# ST7789_Sheet.net
KiCad netlist of a schematic drawn in Altium Designer
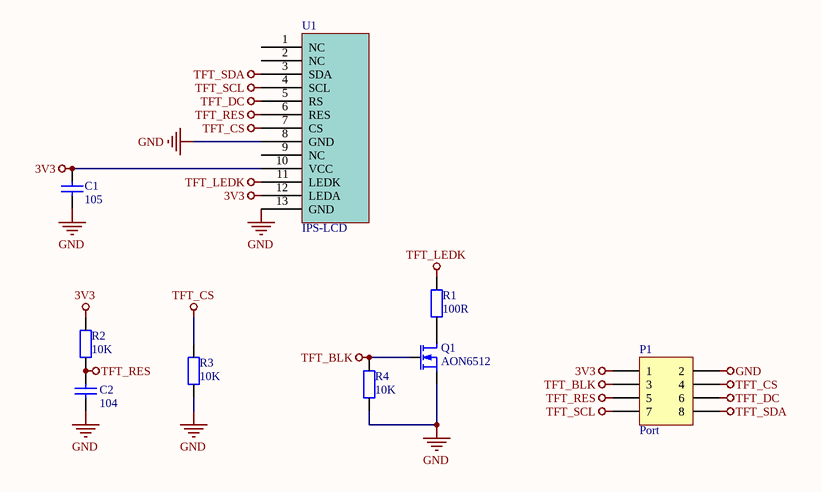
[diagram p0: ST7789_Sheet.SchDoc]

(export (version "E")
  (design (tool "Eeschema 10.0.6"))
  (components
    (comp (ref "C1")
      (value "105")
      (footprint "电容_C0603")
      (fields (field (name "C") "105"))
      (libsource (lib "元件库") (part "cap"))
    )
    (comp (ref "C2")
      (value "104")
      (footprint "电容_C0603")
      (fields (field (name "C") "104"))
      (libsource (lib "元件库") (part "cap"))
    )
    (comp (ref "P1")
      (value "Port")
      (footprint "HDR2X4")
      (description "Header, 4-Pin, Dual row")
      (fields (field (name "PUBLISHER") "Altium Limited"))
      (libsource (lib "Miscellaneous Connectors") (part "Header 4X2"))
    )
    (comp (ref "Q1") (value "AON6512") (footprint "MOS_SOT-23") (libsource (lib "元件库") (part "MOSFET-N")))
    (comp (ref "R1")
      (value "100R")
      (footprint "电阻_R0603")
      (fields (field (name "_VALUE") "100R"))
      (libsource (lib "元件库") (part "Res"))
    )
    (comp (ref "R2")
      (value "10K")
      (footprint "电阻_R0603")
      (fields (field (name "R") "10K"))
      (libsource (lib "元件库") (part "Res"))
    )
    (comp (ref "R3")
      (value "10K")
      (footprint "电阻_R0603")
      (fields (field (name "R") "10K"))
      (libsource (lib "元件库") (part "Res"))
    )
    (comp (ref "R4")
      (value "10K")
      (footprint "电阻_R0603")
      (fields (field (name "R") "10K"))
      (libsource (lib "元件库") (part "Res"))
    )
    (comp (ref "U1")
      (value "IPS-LCD")
      (footprint "TriggersLib:1.14IPS-LCD")
      (description "IPS-LCD-1.14寸裸屏spi接口")
      (libsource (lib "TriggersLib") (part "IPS-LCD-1.14"))
    )
  )
  (nets
    (net (code "1") (name "3V3") (class "Default")
      (node (ref "C1") (pin "2") (pinfunction "2_2") (pintype "passive"))
      (node (ref "P1") (pin "1") (pinfunction "1_1") (pintype "passive"))
      (node (ref "R2") (pin "2") (pinfunction "2_2") (pintype "passive"))
      (node (ref "U1") (pin "10") (pinfunction "VCC_10") (pintype "passive"))
      (node (ref "U1") (pin "12") (pinfunction "LEDA_12") (pintype "passive"))
    )
    (net (code "2") (name "GND") (class "Default")
      (node (ref "C1") (pin "1") (pinfunction "1_1") (pintype "passive"))
      (node (ref "C2") (pin "1") (pinfunction "1_1") (pintype "passive"))
      (node (ref "P1") (pin "2") (pinfunction "2_2") (pintype "passive"))
      (node (ref "Q1") (pin "3") (pinfunction "S_3") (pintype "passive"))
      (node (ref "R3") (pin "1") (pinfunction "1_1") (pintype "passive"))
      (node (ref "R4") (pin "1") (pinfunction "1_1") (pintype "passive"))
      (node (ref "U1") (pin "13") (pinfunction "GND_13") (pintype "passive"))
      (node (ref "U1") (pin "8") (pinfunction "GND_8") (pintype "passive"))
    )
    (net (code "3") (name "Net-(Q1-D)") (class "Default")
      (node (ref "Q1") (pin "2") (pinfunction "D_2") (pintype "passive"))
      (node (ref "R1") (pin "1") (pinfunction "1_1") (pintype "passive"))
    )
    (net (code "4") (name "TFT_BLK") (class "Default")
      (node (ref "P1") (pin "3") (pinfunction "3_3") (pintype "passive"))
      (node (ref "Q1") (pin "1") (pinfunction "G_1") (pintype "passive"))
      (node (ref "R4") (pin "2") (pinfunction "2_2") (pintype "passive"))
    )
    (net (code "5") (name "TFT_CS") (class "Default")
      (node (ref "P1") (pin "4") (pinfunction "4_4") (pintype "passive"))
      (node (ref "R3") (pin "2") (pinfunction "2_2") (pintype "passive"))
      (node (ref "U1") (pin "7") (pinfunction "CS_7") (pintype "passive"))
    )
    (net (code "6") (name "TFT_DC") (class "Default")
      (node (ref "P1") (pin "6") (pinfunction "6_6") (pintype "passive"))
      (node (ref "U1") (pin "5") (pinfunction "RS_5") (pintype "passive"))
    )
    (net (code "7") (name "TFT_LEDK") (class "Default")
      (node (ref "R1") (pin "2") (pinfunction "2_2") (pintype "passive"))
      (node (ref "U1") (pin "11") (pinfunction "LEDK_11") (pintype "passive"))
    )
    (net (code "8") (name "TFT_RES") (class "Default")
      (node (ref "C2") (pin "2") (pinfunction "2_2") (pintype "passive"))
      (node (ref "P1") (pin "5") (pinfunction "5_5") (pintype "passive"))
      (node (ref "R2") (pin "1") (pinfunction "1_1") (pintype "passive"))
      (node (ref "U1") (pin "6") (pinfunction "RES_6") (pintype "passive"))
    )
    (net (code "9") (name "TFT_SCL") (class "Default")
      (node (ref "P1") (pin "7") (pinfunction "7_7") (pintype "passive"))
      (node (ref "U1") (pin "4") (pinfunction "SCL_4") (pintype "passive"))
    )
    (net (code "10") (name "TFT_SDA") (class "Default")
      (node (ref "P1") (pin "8") (pinfunction "8_8") (pintype "passive"))
      (node (ref "U1") (pin "3") (pinfunction "SDA_3") (pintype "passive"))
    )
    (net (code "11") (name "unconnected-(U1-NC-Pad1)") (class "Default")
      (node (ref "U1") (pin "1") (pinfunction "NC_1") (pintype "passive"))
    )
    (net (code "12") (name "unconnected-(U1-NC-Pad2)") (class "Default")
      (node (ref "U1") (pin "2") (pinfunction "NC_2") (pintype "passive"))
    )
    (net (code "13") (name "unconnected-(U1-NC-Pad9)") (class "Default")
      (node (ref "U1") (pin "9") (pinfunction "NC_9") (pintype "passive"))
    )
  )
)
